# batteryholder3S2P_revB.net
KiCad netlist of a schematic drawn in EAGLE
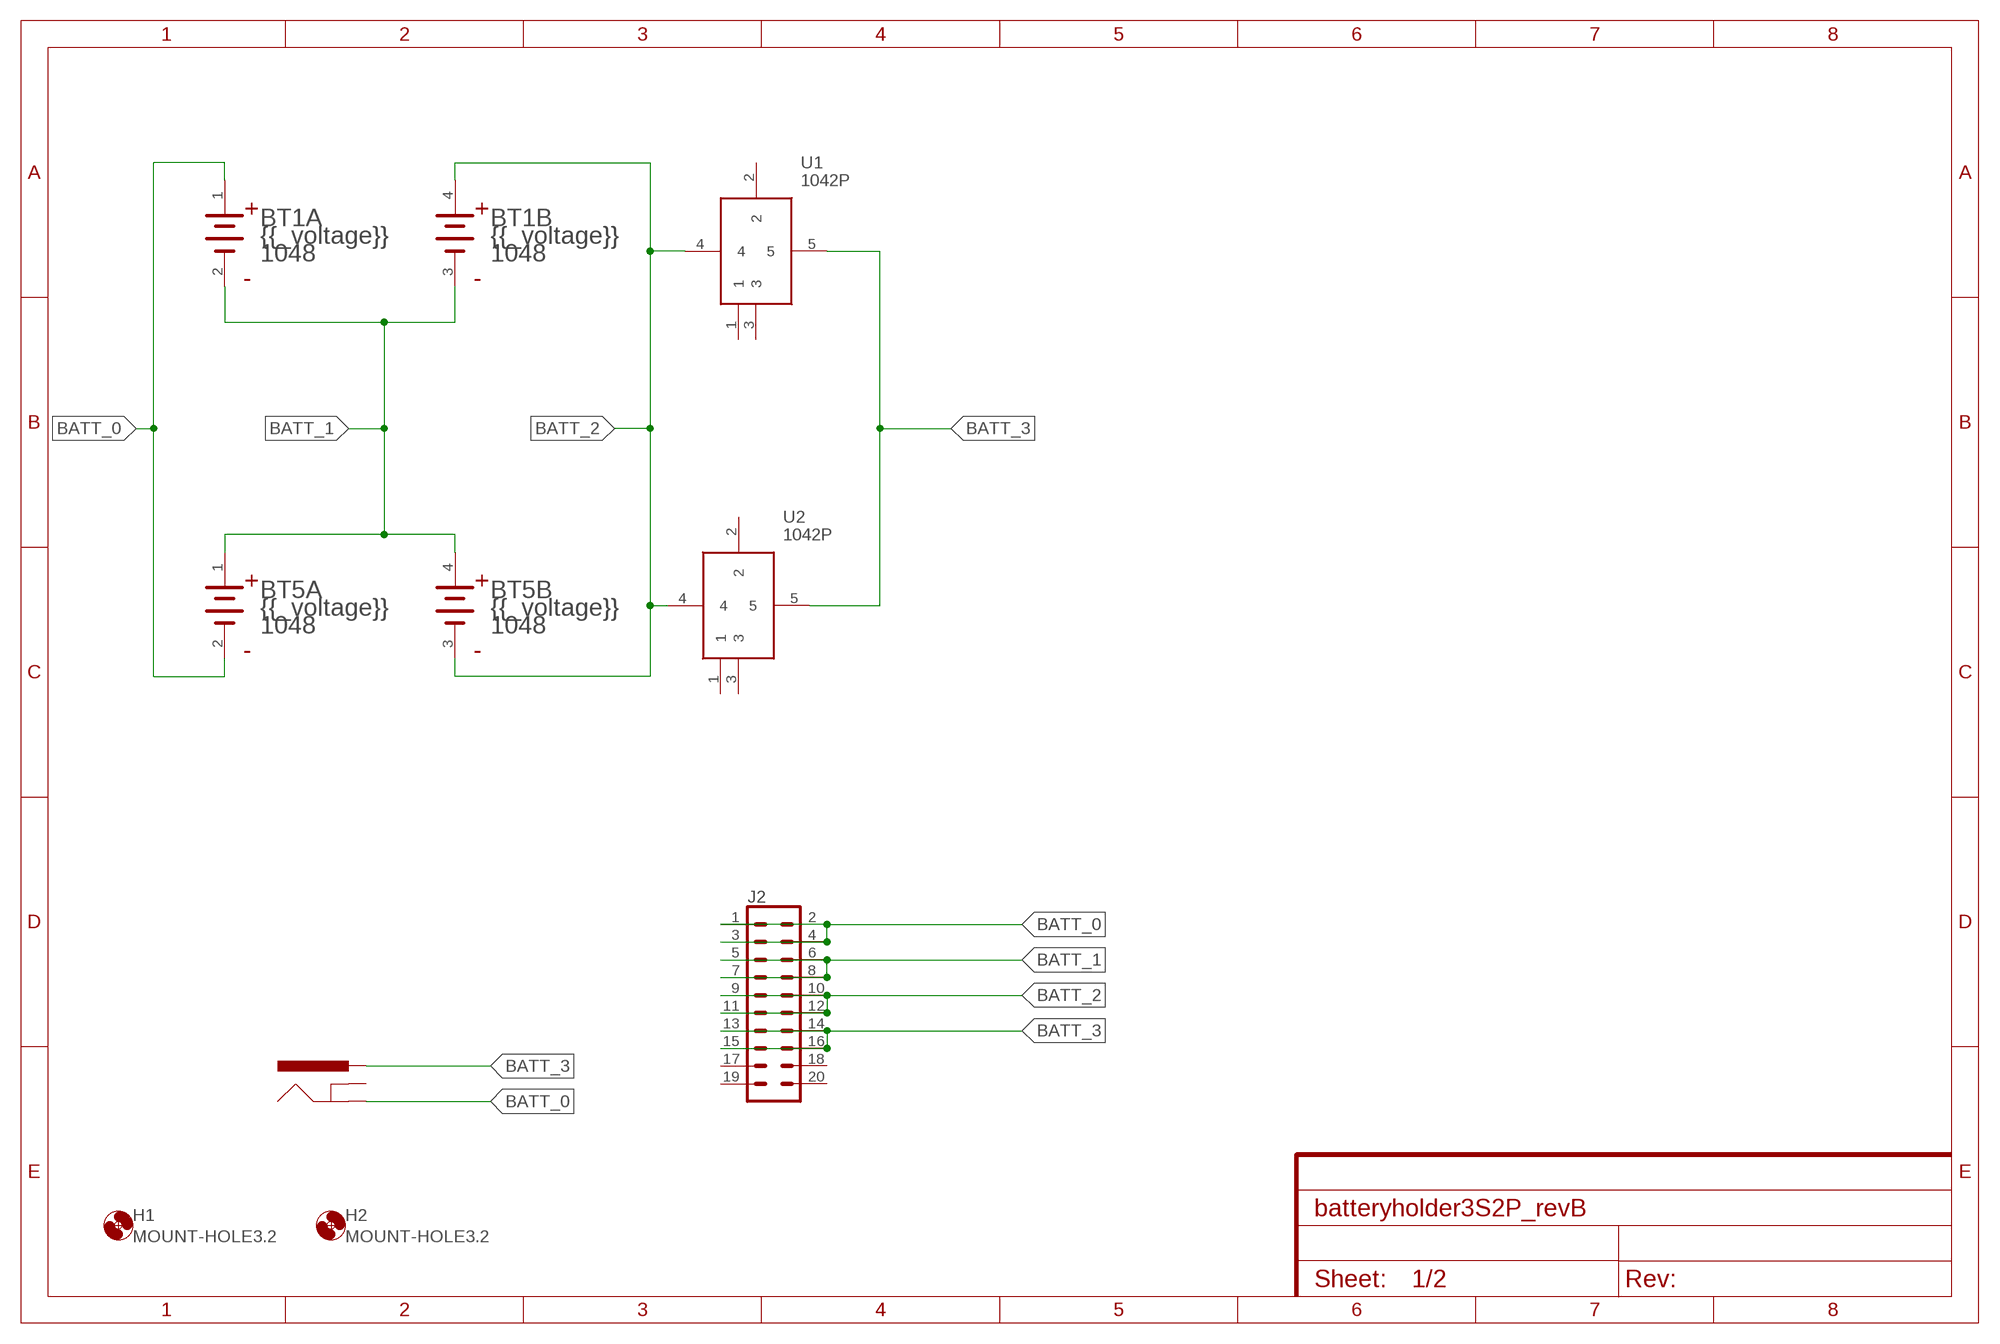
[diagram p0: schematic, sheet 1]

(export (version "E")
  (design (tool "Eeschema 10.0.6"))
  (components
    (comp (ref "BT1")
      (value "KEYSTONE_1048KEYSTONE_1048_0_0")
      (footprint "eagle-import:KEYSTONE_1048_0")
      (fields
        (field (name "DIGIKEY_PART_NUMBER") "36-1048-ND")
        (field (name "MF") "Keystone")
        (field (name "MOUSER_PART_NUMBER") "534-1048")
      )
      (libsource (lib "eagle-import") (part "KEYSTONE_1048KEYSTONE_1048_0_0"))
    )
    (comp (ref "BT5")
      (value "KEYSTONE_1048KEYSTONE_1048_0_0")
      (footprint "eagle-import:KEYSTONE_1048_0")
      (fields
        (field (name "DIGIKEY_PART_NUMBER") "36-1048-ND")
        (field (name "MF") "Keystone")
        (field (name "MOUSER_PART_NUMBER") "534-1048")
      )
      (libsource (lib "eagle-import") (part "KEYSTONE_1048KEYSTONE_1048_0_0"))
    )
    (comp (ref "H1")
      (value "MOUNT-HOLE3.2")
      (footprint "eagle-import:3,2")
      (libsource (lib "eagle-import") (part "MOUNT-HOLE3.2"))
    )
    (comp (ref "H2")
      (value "MOUNT-HOLE3.2")
      (footprint "eagle-import:3,2")
      (libsource (lib "eagle-import") (part "MOUNT-HOLE3.2"))
    )
    (comp (ref "J2")
      (value "CONN_10X2NOSILK")
      (footprint "eagle-import:2X10_NOSILK")
      (libsource (lib "eagle-import") (part "CONN_10X2NOSILK"))
    )
    (comp (ref "J3")
      (value "POWER_JACKPTH_BREAD")
      (footprint "eagle-import:POWER_JACK_PTH_BREAD")
      (libsource (lib "eagle-import") (part "POWER_JACKPTH_BREAD"))
    )
    (comp (ref "U1")
      (value "1042P")
      (footprint "eagle-import:1042P")
      (fields (field (name "MOUSER_PART_NUMBER") "534-1042P"))
      (libsource (lib "eagle-import") (part "1042P"))
    )
    (comp (ref "U2")
      (value "1042P")
      (footprint "eagle-import:1042P")
      (fields (field (name "MOUSER_PART_NUMBER") "534-1042P"))
      (libsource (lib "eagle-import") (part "1042P"))
    )
  )
  (nets
    (net (code "1") (name "BATT_0") (class "Default")
      (node (ref "BT1") (pin "1") (pinfunction "1_ANODE_1") (pintype "passive"))
      (node (ref "BT5") (pin "2") (pinfunction "1_CATHODE_2") (pintype "passive"))
      (node (ref "J2") (pin "1") (pinfunction "1_1") (pintype "passive"))
      (node (ref "J2") (pin "2") (pinfunction "2_2") (pintype "passive"))
      (node (ref "J2") (pin "3") (pinfunction "3_3") (pintype "passive"))
      (node (ref "J2") (pin "4") (pinfunction "4_4") (pintype "passive"))
      (node (ref "J3") (pin "GND") (pinfunction "GND_GND") (pintype "bidirectional"))
    )
    (net (code "2") (name "BATT_1") (class "Default")
      (node (ref "BT1") (pin "2") (pinfunction "1_CATHODE_2") (pintype "passive"))
      (node (ref "BT1") (pin "3") (pinfunction "2_CATHODE_3") (pintype "passive"))
      (node (ref "BT5") (pin "1") (pinfunction "1_ANODE_1") (pintype "passive"))
      (node (ref "BT5") (pin "4") (pinfunction "2_ANODE_4") (pintype "passive"))
      (node (ref "J2") (pin "5") (pinfunction "5_5") (pintype "passive"))
      (node (ref "J2") (pin "6") (pinfunction "6_6") (pintype "passive"))
      (node (ref "J2") (pin "7") (pinfunction "7_7") (pintype "passive"))
      (node (ref "J2") (pin "8") (pinfunction "8_8") (pintype "passive"))
    )
    (net (code "3") (name "BATT_2") (class "Default")
      (node (ref "BT1") (pin "4") (pinfunction "2_ANODE_4") (pintype "passive"))
      (node (ref "BT5") (pin "3") (pinfunction "2_CATHODE_3") (pintype "passive"))
      (node (ref "J2") (pin "10") (pinfunction "10_10") (pintype "passive"))
      (node (ref "J2") (pin "11") (pinfunction "11_11") (pintype "passive"))
      (node (ref "J2") (pin "12") (pinfunction "12_12") (pintype "passive"))
      (node (ref "J2") (pin "9") (pinfunction "9_9") (pintype "passive"))
      (node (ref "U1") (pin "4") (pinfunction "4_4") (pintype "bidirectional"))
      (node (ref "U2") (pin "4") (pinfunction "4_4") (pintype "bidirectional"))
    )
    (net (code "4") (name "BATT_3") (class "Default")
      (node (ref "J2") (pin "13") (pinfunction "13_13") (pintype "passive"))
      (node (ref "J2") (pin "14") (pinfunction "14_14") (pintype "passive"))
      (node (ref "J2") (pin "15") (pinfunction "15_15") (pintype "passive"))
      (node (ref "J2") (pin "16") (pinfunction "16_16") (pintype "passive"))
      (node (ref "J3") (pin "PWR") (pinfunction "PWR_PWR") (pintype "bidirectional"))
      (node (ref "U1") (pin "5") (pinfunction "5_5") (pintype "bidirectional"))
      (node (ref "U2") (pin "5") (pinfunction "5_5") (pintype "bidirectional"))
    )
    (net (code "5") (name "unconnected-(J2-Pad17)") (class "Default")
      (node (ref "J2") (pin "17") (pinfunction "17_17") (pintype "passive"))
    )
    (net (code "6") (name "unconnected-(J2-Pad18)") (class "Default")
      (node (ref "J2") (pin "18") (pinfunction "18_18") (pintype "passive"))
    )
    (net (code "7") (name "unconnected-(J2-Pad19)") (class "Default")
      (node (ref "J2") (pin "19") (pinfunction "19_19") (pintype "passive"))
    )
    (net (code "8") (name "unconnected-(J2-Pad20)") (class "Default")
      (node (ref "J2") (pin "20") (pinfunction "20_20") (pintype "passive"))
    )
    (net (code "9") (name "unconnected-(J3-PadGNDBREAK)") (class "Default")
      (node (ref "J3") (pin "GNDBREAK") (pinfunction "GNDBREAK_GNDBREAK") (pintype "bidirectional"))
    )
    (net (code "10") (name "unconnected-(U1-Pad1)") (class "Default")
      (node (ref "U1") (pin "1") (pinfunction "1_1") (pintype "bidirectional"))
    )
    (net (code "11") (name "unconnected-(U1-Pad2)") (class "Default")
      (node (ref "U1") (pin "2") (pinfunction "2_2") (pintype "bidirectional"))
    )
    (net (code "12") (name "unconnected-(U1-Pad3)") (class "Default")
      (node (ref "U1") (pin "3") (pinfunction "3_3") (pintype "bidirectional"))
    )
    (net (code "13") (name "unconnected-(U2-Pad1)") (class "Default")
      (node (ref "U2") (pin "1") (pinfunction "1_1") (pintype "bidirectional"))
    )
    (net (code "14") (name "unconnected-(U2-Pad2)") (class "Default")
      (node (ref "U2") (pin "2") (pinfunction "2_2") (pintype "bidirectional"))
    )
    (net (code "15") (name "unconnected-(U2-Pad3)") (class "Default")
      (node (ref "U2") (pin "3") (pinfunction "3_3") (pintype "bidirectional"))
    )
  )
)
